# Sheet1.net
KiCad netlist of a schematic drawn in Altium Designer
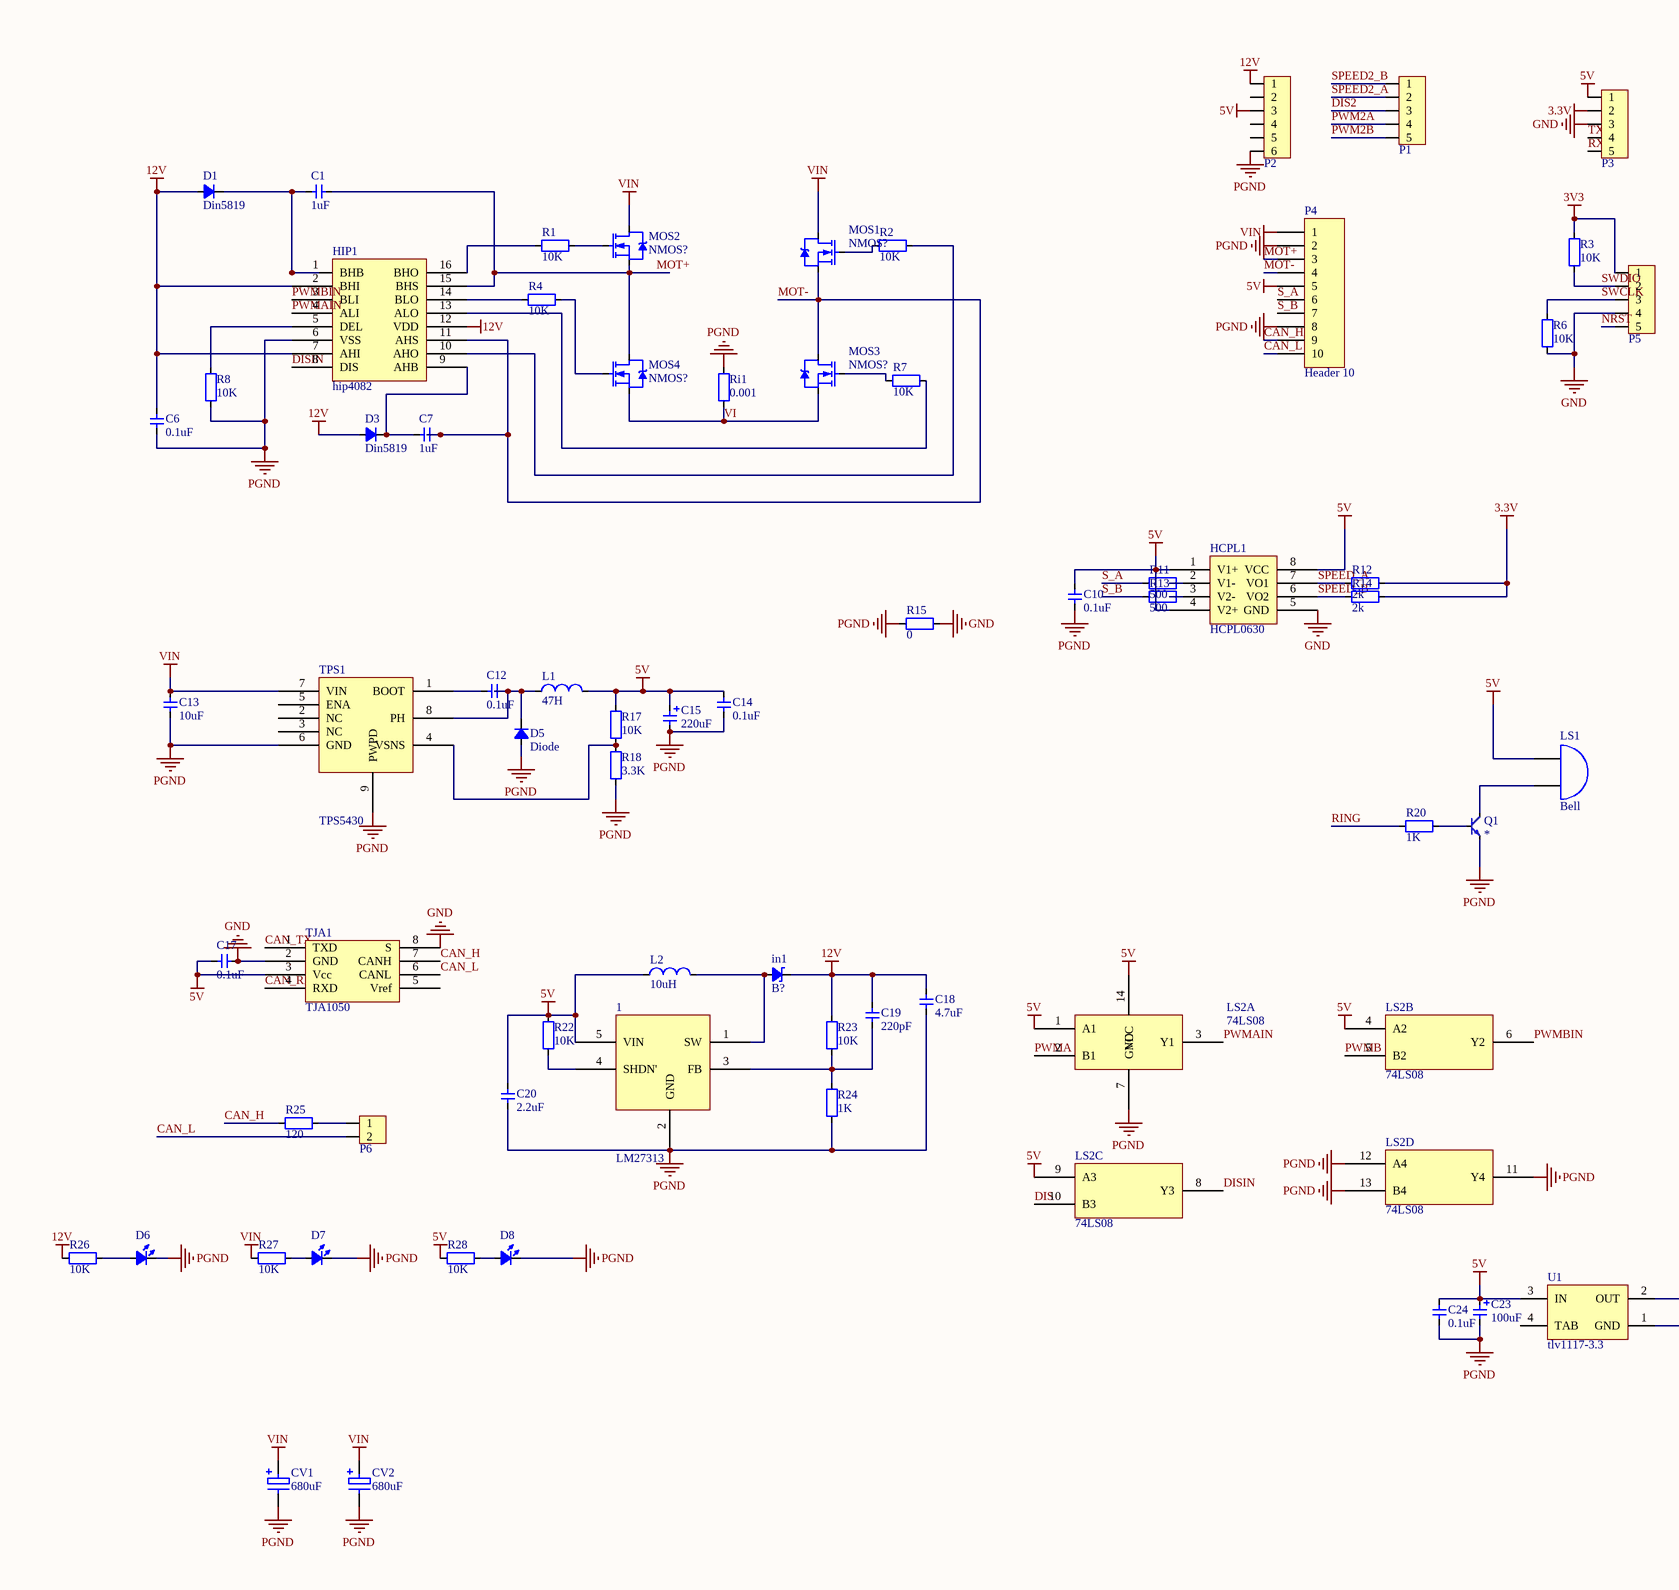
[diagram p0: Sheet1.SchDoc, left]
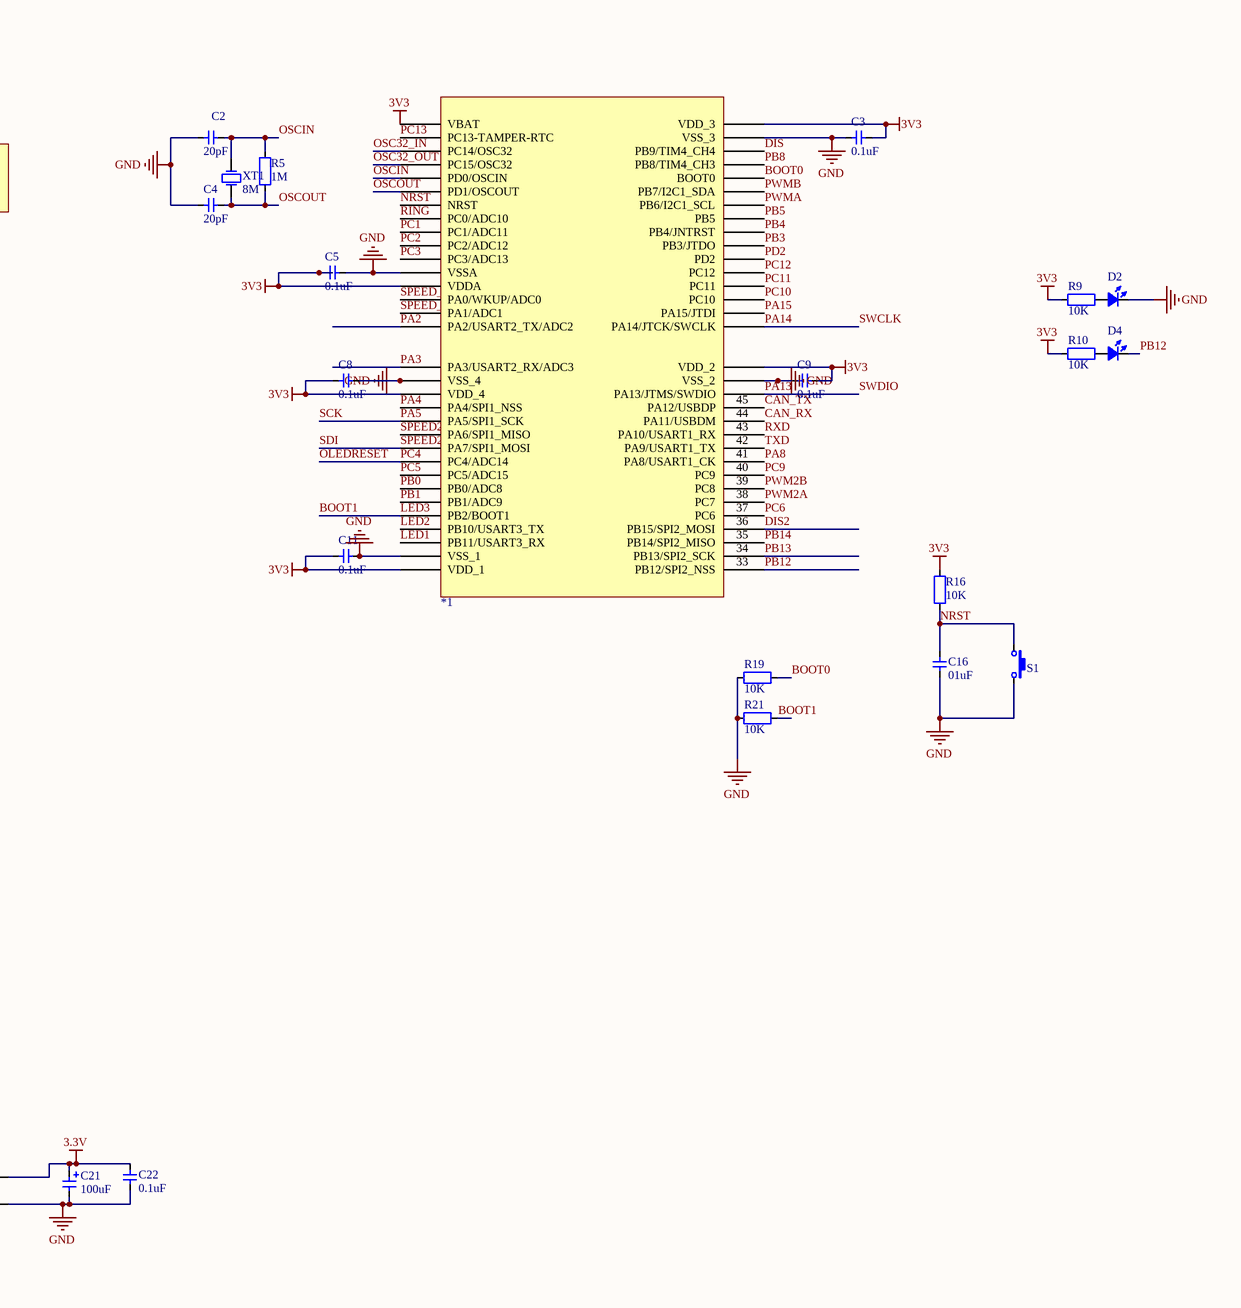
[diagram p1: Sheet1.SchDoc, right]

(export (version "E")
  (design (tool "Eeschema 10.0.6"))
  (components
    (comp (ref "*1")
      (value "STM32F103RC")
      (footprint "LQFP_P0.5_64")
      (description "MCU")
      (libsource (lib "Integrated_Library") (part "STM32F103RC"))
    )
    (comp (ref "1")
      (value "LM27313")
      (footprint "SOT23-5")
      (libsource (lib "K60-mainboard-v3.1") (part "LM27313"))
    )
    (comp (ref "C1")
      (value "1uF")
      (footprint "CAP_0603")
      (description "Capacitor")
      (fields (field (name "Comment") "Cap_0603"))
      (libsource (lib "Integrated_Library") (part "Cap_0603"))
    )
    (comp (ref "C2")
      (value "20pF")
      (footprint "CAP_0603")
      (description "Capacitor")
      (fields (field (name "Comment") "Cap_0603"))
      (libsource (lib "Integrated_Library") (part "Cap_0603"))
    )
    (comp (ref "C3")
      (value "0.1uF")
      (footprint "CAP_0603")
      (description "Capacitor")
      (fields (field (name "Comment") "Cap_0603"))
      (libsource (lib "Integrated_Library") (part "Cap_0603"))
    )
    (comp (ref "C4")
      (value "20pF")
      (footprint "CAP_0603")
      (description "Capacitor")
      (fields (field (name "Comment") "Cap_0603"))
      (libsource (lib "Integrated_Library") (part "Cap_0603"))
    )
    (comp (ref "C5")
      (value "0.1uF")
      (footprint "CAP_0603")
      (description "Capacitor")
      (fields (field (name "Comment") "Cap_0603"))
      (libsource (lib "Integrated_Library") (part "Cap_0603"))
    )
    (comp (ref "C6")
      (value "0.1uF")
      (footprint "CAP_0603")
      (description "Capacitor")
      (fields (field (name "Comment") "Cap_0603"))
      (libsource (lib "Integrated_Library") (part "Cap_0603"))
    )
    (comp (ref "C7")
      (value "1uF")
      (footprint "CAP_0603")
      (description "Capacitor")
      (fields (field (name "Comment") "Cap_0603"))
      (libsource (lib "Integrated_Library") (part "Cap_0603"))
    )
    (comp (ref "C8")
      (value "0.1uF")
      (footprint "CAP_0603")
      (description "Capacitor")
      (fields (field (name "Comment") "Cap_0603"))
      (libsource (lib "Integrated_Library") (part "Cap_0603"))
    )
    (comp (ref "C9")
      (value "0.1uF")
      (footprint "CAP_0603")
      (description "Capacitor")
      (fields (field (name "Comment") "Cap_0603"))
      (libsource (lib "Integrated_Library") (part "Cap_0603"))
    )
    (comp (ref "C10")
      (value "0.1uF")
      (footprint "CAP_0603")
      (description "Capacitor")
      (fields (field (name "Comment") "Cap_0603"))
      (libsource (lib "Integrated_Library") (part "Cap_0603"))
    )
    (comp (ref "C11")
      (value "0.1uF")
      (footprint "CAP_0603")
      (description "Capacitor")
      (fields (field (name "Comment") "Cap_0603"))
      (libsource (lib "Integrated_Library") (part "Cap_0603"))
    )
    (comp (ref "C12")
      (value "0.1uF")
      (footprint "CAP_0603")
      (description "Capacitor")
      (fields (field (name "Comment") "Cap_0603"))
      (libsource (lib "Integrated_Library") (part "Cap_0603"))
    )
    (comp (ref "C13")
      (value "10uF")
      (footprint "CAP_0603")
      (description "Capacitor")
      (fields (field (name "Comment") "Cap_0603"))
      (libsource (lib "Integrated_Library") (part "Cap_0603"))
    )
    (comp (ref "C14")
      (value "0.1uF")
      (footprint "CAP_0603")
      (description "Capacitor")
      (fields (field (name "Comment") "Cap_0603"))
      (libsource (lib "Integrated_Library") (part "Cap_0603"))
    )
    (comp (ref "C15")
      (value "220uF")
      (footprint "CAP_TAN_P0805")
      (description "Capacitor")
      (fields (field (name "Comment") "Cap_Tan_0805"))
      (libsource (lib "Integrated_Library") (part "Cap_Tan_0805"))
    )
    (comp (ref "C16")
      (value "01uF")
      (footprint "CAP_0603")
      (description "Capacitor")
      (fields (field (name "Comment") "Cap_0603"))
      (libsource (lib "Integrated_Library") (part "Cap_0603"))
    )
    (comp (ref "C17")
      (value "0.1uF")
      (footprint "CAP_0603")
      (description "Capacitor")
      (fields (field (name "Comment") "Cap_0603"))
      (libsource (lib "Integrated_Library") (part "Cap_0603"))
    )
    (comp (ref "C18")
      (value "4.7uF")
      (footprint "CAP_0603")
      (description "Capacitor")
      (fields (field (name "Comment") "Cap_0603"))
      (libsource (lib "Integrated_Library") (part "Cap_0603"))
    )
    (comp (ref "C19")
      (value "220pF")
      (footprint "CAP_0603")
      (description "Capacitor")
      (fields (field (name "Comment") "Cap_0603"))
      (libsource (lib "Integrated_Library") (part "Cap_0603"))
    )
    (comp (ref "C20")
      (value "2.2uF")
      (footprint "CAP_0603")
      (description "Capacitor")
      (fields (field (name "Comment") "Cap_0603"))
      (libsource (lib "Integrated_Library") (part "Cap_0603"))
    )
    (comp (ref "C21")
      (value "100uF")
      (footprint "CAP_TAN_P0805")
      (description "Capacitor")
      (fields (field (name "Comment") "Cap_Tan_0805"))
      (libsource (lib "Integrated_Library") (part "Cap_Tan_0805"))
    )
    (comp (ref "C22")
      (value "0.1uF")
      (footprint "CAP_0603")
      (description "Capacitor")
      (fields (field (name "Comment") "Cap_0603"))
      (libsource (lib "Integrated_Library") (part "Cap_0603"))
    )
    (comp (ref "C23")
      (value "100uF")
      (footprint "CAP_TAN_P0805")
      (description "Capacitor")
      (fields (field (name "Comment") "Cap_Tan_0805"))
      (libsource (lib "Integrated_Library") (part "Cap_Tan_0805"))
    )
    (comp (ref "C24")
      (value "0.1uF")
      (footprint "CAP_0603")
      (description "Capacitor")
      (fields (field (name "Comment") "Cap_0603"))
      (libsource (lib "Integrated_Library") (part "Cap_0603"))
    )
    (comp (ref "CV1")
      (value "680uF")
      (footprint "电解电容器")
      (description "电解电容")
      (fields (field (name "PUBLISHER") "Altium Limited"))
      (libsource (lib "Libraries_2014_0618") (part "CAP-ELE"))
    )
    (comp (ref "CV2")
      (value "680uF")
      (footprint "电解电容器")
      (description "电解电容")
      (fields (field (name "PUBLISHER") "Altium Limited"))
      (libsource (lib "Libraries_2014_0618") (part "CAP-ELE"))
    )
    (comp (ref "D1")
      (value "Din5819")
      (footprint "LED_0805_RED")
      (description "Diode")
      (libsource (lib "Integrated_Library") (part "Diode"))
    )
    (comp (ref "D2")
      (value "LED_0805")
      (footprint "LED_0805_RED")
      (description "LED")
      (libsource (lib "Integrated_Library") (part "LED_0805"))
    )
    (comp (ref "D3")
      (value "Din5819")
      (footprint "LED_0805_RED")
      (description "Diode")
      (libsource (lib "Integrated_Library") (part "Diode"))
    )
    (comp (ref "D4")
      (value "LED_0805")
      (footprint "LED_0805_RED")
      (description "LED")
      (libsource (lib "Integrated_Library") (part "LED_0805"))
    )
    (comp (ref "D5") (value "Diode") (footprint "LED_0805_RED") (libsource (lib "SCH_Active") (part "Diode")))
    (comp (ref "D6")
      (value "LED_0603")
      (footprint "PCB_ActiveLED:LED_0603_RED")
      (description "LED")
      (libsource (lib "SCH_Active") (part "LED_0603"))
    )
    (comp (ref "D7")
      (value "LED_0603")
      (footprint "PCB_ActiveLED:LED_0603_RED")
      (description "LED")
      (libsource (lib "SCH_Active") (part "LED_0603"))
    )
    (comp (ref "D8")
      (value "LED_0603")
      (footprint "PCB_ActiveLED:LED_0603_RED")
      (description "LED")
      (libsource (lib "SCH_Active") (part "LED_0603"))
    )
    (comp (ref "HCPL1")
      (value "HCPL0630")
      (footprint "SOP_E150_8")
      (libsource (lib "K60-mainboard-v3.1") (part "HCPL0630"))
    )
    (comp (ref "HIP1") (value "hip4082") (footprint "SOP_E150_16") (libsource (lib "元件库") (part "hip4082")))
    (comp (ref "in1")
      (value "B?")
      (footprint "PCB_ActiveDIO:SOD-123")
      (description "Diode")
      (fields (field (name "Comment") "SchottkyDiode_SOD123"))
      (libsource (lib "SCH_Active") (part "SchottkyDiode_SOD123"))
    )
    (comp (ref "L1")
      (value "47H")
      (footprint "IND_0603")
      (description "Inductor")
      (fields (field (name "Comment") "Ind_0603"))
      (libsource (lib "Integrated_Library") (part "Ind_0603"))
    )
    (comp (ref "L2")
      (value "10uH")
      (footprint "IND_0603")
      (description "Inductor")
      (fields (field (name "Comment") "Ind_0603"))
      (libsource (lib "Integrated_Library") (part "Ind_0603"))
    )
    (comp (ref "LS1")
      (value "Bell")
      (footprint "Bell-5.6-0.6-9mm")
      (description "Electrical Bell")
      (fields (field (name "PUBLISHER") "Altium Limited"))
      (libsource (lib "附加元件") (part "Bell"))
    )
    (comp (ref "LS2")
      (value "74LS08")
      (footprint "SOP14")
      (libsource (lib "K60-mainboard-v3.1") (part "74LS08"))
    )
    (comp (ref "MOS1")
      (value "NMOS?")
      (footprint "PCB_IntegratedCircuit:TO-252AA")
      (description "MOSFET")
      (fields (field (name "Comment") "MOSFET_N"))
      (libsource (lib "SCH_Active") (part "MOSFET_N"))
    )
    (comp (ref "MOS2")
      (value "NMOS?")
      (footprint "PCB_IntegratedCircuit:TO-252AA")
      (description "MOSFET")
      (fields (field (name "Comment") "MOSFET_N"))
      (libsource (lib "SCH_Active") (part "MOSFET_N"))
    )
    (comp (ref "MOS3")
      (value "NMOS?")
      (footprint "PCB_IntegratedCircuit:TO-252AA")
      (description "MOSFET")
      (fields (field (name "Comment") "MOSFET_N"))
      (libsource (lib "SCH_Active") (part "MOSFET_N"))
    )
    (comp (ref "MOS4")
      (value "NMOS?")
      (footprint "PCB_IntegratedCircuit:TO-252AA")
      (description "MOSFET")
      (fields (field (name "Comment") "MOSFET_N"))
      (libsource (lib "SCH_Active") (part "MOSFET_N"))
    )
    (comp (ref "P1")
      (value "HDR1x5_2.54")
      (footprint "HDR1X5_2.54_180")
      (description "Header")
      (libsource (lib "Integrated_Library") (part "HDR1x5_2.54"))
    )
    (comp (ref "P2")
      (value "HDR1x6_2.54")
      (footprint "HDR1X6_2.54_180")
      (description "Header")
      (libsource (lib "Integrated_Library") (part "HDR1x6_2.54"))
    )
    (comp (ref "P3")
      (value "HDR1x5_2.54")
      (footprint "Green_5P")
      (description "Header")
      (libsource (lib "Integrated_Library") (part "HDR1x5_2.54"))
    )
    (comp (ref "P4")
      (value "Header 10")
      (footprint "Green_10P")
      (description "Header, 10-Pin")
      (fields (field (name "PUBLISHER") "Altium Limited"))
      (libsource (lib "Libraries_2014_0618") (part "Header 10"))
    )
    (comp (ref "P5")
      (value "HDR1x5_2.54")
      (footprint "HDR1X5_2.54_180")
      (description "Header")
      (libsource (lib "Integrated_Library") (part "HDR1x5_2.54"))
    )
    (comp (ref "P6")
      (value "HDR1x2_2.54")
      (footprint "HDR1X2_2.54_180")
      (description "Header")
      (libsource (lib "Integrated_Library") (part "HDR1x2_2.54"))
    )
    (comp (ref "Q1")
      (value "BJT_NPN")
      (footprint "SOT23-3")
      (description "Transistor")
      (fields (field (name "ALTIUM_VALUE") "*"))
      (libsource (lib "Integrated_Library") (part "BJT_NPN"))
    )
    (comp (ref "R1")
      (value "10K")
      (footprint "RES_0603")
      (description "Resistor")
      (fields (field (name "Comment") "Res_0603"))
      (libsource (lib "Integrated_Library") (part "Res_0603"))
    )
    (comp (ref "R2")
      (value "10K")
      (footprint "RES_0603")
      (description "Resistor")
      (fields (field (name "Comment") "Res_0603"))
      (libsource (lib "Integrated_Library") (part "Res_0603"))
    )
    (comp (ref "R3")
      (value "10K")
      (footprint "RES_0603")
      (description "Resistor")
      (fields (field (name "Comment") "Res_0603"))
      (libsource (lib "") (part "Res_0603_2"))
    )
    (comp (ref "R4")
      (value "10K")
      (footprint "RES_0603")
      (description "Resistor")
      (fields (field (name "Comment") "Res_0603"))
      (libsource (lib "Integrated_Library") (part "Res_0603"))
    )
    (comp (ref "R5")
      (value "1M")
      (footprint "RES_0603")
      (description "Resistor")
      (fields (field (name "Comment") "Res_0603"))
      (libsource (lib "") (part "Res_0603_2"))
    )
    (comp (ref "R6")
      (value "10K")
      (footprint "RES_0603")
      (description "Resistor")
      (fields (field (name "Comment") "Res_0603"))
      (libsource (lib "") (part "Res_0603_2"))
    )
    (comp (ref "R7")
      (value "10K")
      (footprint "RES_0603")
      (description "Resistor")
      (fields (field (name "Comment") "Res_0603"))
      (libsource (lib "Integrated_Library") (part "Res_0603"))
    )
    (comp (ref "R8")
      (value "10K")
      (footprint "RES_0603")
      (description "Resistor")
      (fields (field (name "Comment") "Res_0603"))
      (libsource (lib "") (part "Res_0603_2"))
    )
    (comp (ref "R9")
      (value "10K")
      (footprint "RES_0603")
      (description "Resistor")
      (fields (field (name "Comment") "Res_0603"))
      (libsource (lib "Integrated_Library") (part "Res_0603"))
    )
    (comp (ref "R10")
      (value "10K")
      (footprint "RES_0603")
      (description "Resistor")
      (fields (field (name "Comment") "Res_0603"))
      (libsource (lib "Integrated_Library") (part "Res_0603"))
    )
    (comp (ref "R11")
      (value "500")
      (footprint "RES_0603")
      (description "Resistor")
      (fields (field (name "Comment") "Res_0603"))
      (libsource (lib "") (part "Res_0603_1"))
    )
    (comp (ref "R12")
      (value "2k")
      (footprint "RES_0603")
      (description "Resistor")
      (fields (field (name "Comment") "Res_0603"))
      (libsource (lib "") (part "Res_0603_1"))
    )
    (comp (ref "R13")
      (value "500")
      (footprint "RES_0603")
      (description "Resistor")
      (fields (field (name "Comment") "Res_0603"))
      (libsource (lib "") (part "Res_0603_1"))
    )
    (comp (ref "R14")
      (value "2k")
      (footprint "RES_0603")
      (description "Resistor")
      (fields (field (name "Comment") "Res_0603"))
      (libsource (lib "") (part "Res_0603_1"))
    )
    (comp (ref "R15")
      (value "0")
      (footprint "RES_0603")
      (description "Resistor")
      (fields (field (name "Comment") "Res_0603"))
      (libsource (lib "Integrated_Library") (part "Res_0603"))
    )
    (comp (ref "R16")
      (value "10K")
      (footprint "RES_0603")
      (description "Resistor")
      (fields (field (name "Comment") "Res_0603"))
      (libsource (lib "") (part "Res_0603_2"))
    )
    (comp (ref "R17")
      (value "10K")
      (footprint "RES_0603")
      (description "Resistor")
      (fields (field (name "Comment") "Res_0603"))
      (libsource (lib "") (part "Res_0603_2"))
    )
    (comp (ref "R18")
      (value "3.3K")
      (footprint "RES_0603")
      (description "Resistor")
      (fields (field (name "Comment") "Res_0603"))
      (libsource (lib "") (part "Res_0603_2"))
    )
    (comp (ref "R19")
      (value "10K")
      (footprint "RES_0603")
      (description "Resistor")
      (fields (field (name "Comment") "Res_0603"))
      (libsource (lib "") (part "Res_0603_1"))
    )
    (comp (ref "R20")
      (value "1K")
      (footprint "RES_0603")
      (description "Resistor")
      (fields (field (name "Comment") "Res_0603"))
      (libsource (lib "Integrated_Library") (part "Res_0603"))
    )
    (comp (ref "R21")
      (value "10K")
      (footprint "RES_0603")
      (description "Resistor")
      (fields (field (name "Comment") "Res_0603"))
      (libsource (lib "") (part "Res_0603_1"))
    )
    (comp (ref "R22")
      (value "10K")
      (footprint "RES_0603")
      (description "Resistor")
      (fields (field (name "Comment") "Res_0603"))
      (libsource (lib "") (part "Res_0603_2"))
    )
    (comp (ref "R23")
      (value "10K")
      (footprint "RES_0603")
      (description "Resistor")
      (fields (field (name "Comment") "Res_0603"))
      (libsource (lib "") (part "Res_0603_2"))
    )
    (comp (ref "R24")
      (value "1K")
      (footprint "RES_0603")
      (description "Resistor")
      (fields (field (name "Comment") "Res_0603"))
      (libsource (lib "") (part "Res_0603_2"))
    )
    (comp (ref "R25")
      (value "120")
      (footprint "RES_0603")
      (description "Resistor")
      (fields (field (name "Comment") "Res_0603"))
      (libsource (lib "Integrated_Library") (part "Res_0603"))
    )
    (comp (ref "R26")
      (value "10K")
      (footprint "RES_0603")
      (description "Resistor")
      (fields (field (name "Comment") "Res_0603"))
      (libsource (lib "Integrated_Library") (part "Res_0603"))
    )
    (comp (ref "R27")
      (value "10K")
      (footprint "RES_0603")
      (description "Resistor")
      (fields (field (name "Comment") "Res_0603"))
      (libsource (lib "Integrated_Library") (part "Res_0603"))
    )
    (comp (ref "R28")
      (value "10K")
      (footprint "RES_0603")
      (description "Resistor")
      (fields (field (name "Comment") "Res_0603"))
      (libsource (lib "Integrated_Library") (part "Res_0603"))
    )
    (comp (ref "Ri1")
      (value "0.001")
      (footprint "RES_0603")
      (description "Resistor")
      (fields (field (name "Comment") "Res_0603"))
      (libsource (lib "") (part "Res_0603_2"))
    )
    (comp (ref "S1")
      (value "ButtonTACT_3x6x2.5_180")
      (footprint "ButtonTACT_3x6x2.5_180")
      (description "Button")
      (libsource (lib "Integrated_Library") (part "ButtonTACT_3x6x2.5_180"))
    )
    (comp (ref "TJA1")
      (value "TJA1050")
      (footprint "SOP_E150_8")
      (description "CAN总线收发器")
      (libsource (lib "Libraries_2014_0618") (part "TJA1050"))
    )
    (comp (ref "TPS1")
      (value "TPS5430")
      (footprint "SOP_E150_9")
      (libsource (lib "K60-mainboard-v3.1") (part "TPS5430"))
    )
    (comp (ref "U1")
      (value "tlv1117-3.3")
      (footprint "SOT223-3")
      (description "800mA Low-Dropout Linear Regulator")
      (fields
        (field (name "PARTNUMBER") "LM1117IMP-5.0")
        (field (name "MANUFACTURER") "National Semiconductor")
        (field (name "PUBLISHER") "Altium Limited")
      )
      (libsource (lib "K60-mainboard-v3.1") (part "LM1117IMP-5.0"))
    )
    (comp (ref "XT1")
      (value "8M")
      (footprint "XT_5032_2")
      (description "Crystal Oscillator")
      (fields (field (name "Comment") "XTAL_32.768kHz"))
      (libsource (lib "Integrated_Library") (part "XTAL_32.768k"))
    )
  )
  (nets
    (net (code "1") (name "/BOOT0") (class "Default")
      (node (ref "*1") (pin "60") (pinfunction "BOOT0_60") (pintype "passive"))
      (node (ref "R19") (pin "1") (pinfunction "1_1") (pintype "passive"))
    )
    (net (code "2") (name "/BOOT1") (class "Default")
      (node (ref "*1") (pin "28") (pinfunction "PB2/BOOT1_28") (pintype "passive"))
      (node (ref "R21") (pin "1") (pinfunction "1_1") (pintype "passive"))
    )
    (net (code "3") (name "/CAN_H") (class "Default")
      (node (ref "P4") (pin "9") (pinfunction "9_9") (pintype "passive"))
      (node (ref "R25") (pin "1") (pinfunction "1_1") (pintype "passive"))
      (node (ref "TJA1") (pin "7") (pinfunction "CANH_7") (pintype "passive"))
    )
    (net (code "4") (name "/CAN_L") (class "Default")
      (node (ref "P4") (pin "10") (pinfunction "10_10") (pintype "passive"))
      (node (ref "P6") (pin "2") (pinfunction "2_2") (pintype "passive"))
      (node (ref "TJA1") (pin "6") (pinfunction "CANL_6") (pintype "passive"))
    )
    (net (code "5") (name "/CAN_RX") (class "Default")
      (node (ref "*1") (pin "44") (pinfunction "PA11/USBDM_44") (pintype "passive"))
      (node (ref "TJA1") (pin "4") (pinfunction "RXD_4") (pintype "passive"))
    )
    (net (code "6") (name "/CAN_TX") (class "Default")
      (node (ref "*1") (pin "45") (pinfunction "PA12/USBDP_45") (pintype "passive"))
      (node (ref "TJA1") (pin "1") (pinfunction "TXD_1") (pintype "passive"))
    )
    (net (code "7") (name "/DIS") (class "Default")
      (node (ref "*1") (pin "62") (pinfunction "PB9/TIM4_CH4_62") (pintype "passive"))
      (node (ref "LS2") (pin "10") (pinfunction "B3_10") (pintype "passive"))
    )
    (net (code "8") (name "/DIS2") (class "Default")
      (node (ref "*1") (pin "36") (pinfunction "PB15/SPI2_MOSI_36") (pintype "passive"))
      (node (ref "P1") (pin "3") (pinfunction "3_3") (pintype "passive"))
    )
    (net (code "9") (name "/DISIN") (class "Default")
      (node (ref "HIP1") (pin "8") (pinfunction "DIS_8") (pintype "passive"))
      (node (ref "LS2") (pin "8") (pinfunction "Y3_8") (pintype "passive"))
    )
    (net (code "10") (name "/LED1") (class "Default")
      (node (ref "*1") (pin "30") (pinfunction "PB11/USART3_RX_30") (pintype "passive"))
    )
    (net (code "11") (name "/LED2") (class "Default")
      (node (ref "*1") (pin "29") (pinfunction "PB10/USART3_TX_29") (pintype "passive"))
    )
    (net (code "12") (name "/MOT+") (class "Default")
      (node (ref "C1") (pin "2") (pinfunction "2_2") (pintype "passive"))
      (node (ref "HIP1") (pin "15") (pinfunction "BHS_15") (pintype "passive"))
      (node (ref "MOS2") (pin "3") (pinfunction "S_3") (pintype "passive"))
      (node (ref "MOS4") (pin "4") (pinfunction "D_4") (pintype "passive"))
      (node (ref "P4") (pin "3") (pinfunction "3_3") (pintype "passive"))
    )
    (net (code "13") (name "/MOT-") (class "Default")
      (node (ref "C7") (pin "2") (pinfunction "2_2") (pintype "passive"))
      (node (ref "HIP1") (pin "11") (pinfunction "AHS_11") (pintype "passive"))
      (node (ref "MOS1") (pin "3") (pinfunction "S_3") (pintype "passive"))
      (node (ref "MOS3") (pin "4") (pinfunction "D_4") (pintype "passive"))
      (node (ref "P4") (pin "4") (pinfunction "4_4") (pintype "passive"))
    )
    (net (code "14") (name "/NRST") (class "Default")
      (node (ref "*1") (pin "7") (pinfunction "NRST_7") (pintype "passive"))
      (node (ref "C16") (pin "2") (pinfunction "2_2") (pintype "passive"))
      (node (ref "P5") (pin "5") (pinfunction "5_5") (pintype "passive"))
      (node (ref "R16") (pin "1") (pinfunction "1_1") (pintype "passive"))
      (node (ref "S1") (pin "1") (pinfunction "1_1") (pintype "passive"))
    )
    (net (code "15") (name "/OLEDRESET") (class "Default")
      (node (ref "*1") (pin "24") (pinfunction "PC4/ADC14_24") (pintype "passive"))
    )
    (net (code "16") (name "/OSC32_IN") (class "Default")
      (node (ref "*1") (pin "3") (pinfunction "PC14/OSC32_3") (pintype "passive"))
    )
    (net (code "17") (name "/OSC32_OUT") (class "Default")
      (node (ref "*1") (pin "4") (pinfunction "PC15/OSC32_4") (pintype "passive"))
    )
    (net (code "18") (name "/OSCIN") (class "Default")
      (node (ref "*1") (pin "5") (pinfunction "PD0/OSCIN_5") (pintype "passive"))
      (node (ref "C2") (pin "2") (pinfunction "2_2") (pintype "passive"))
      (node (ref "R5") (pin "2") (pinfunction "2_2") (pintype "passive"))
      (node (ref "XT1") (pin "2") (pinfunction "OSC2_2") (pintype "passive"))
    )
    (net (code "19") (name "/OSCOUT") (class "Default")
      (node (ref "*1") (pin "6") (pinfunction "PD1/OSCOUT_6") (pintype "passive"))
      (node (ref "C4") (pin "2") (pinfunction "2_2") (pintype "passive"))
      (node (ref "R5") (pin "1") (pinfunction "1_1") (pintype "passive"))
      (node (ref "XT1") (pin "1") (pinfunction "OSC1_1") (pintype "passive"))
    )
    (net (code "20") (name "/PA2") (class "Default")
      (node (ref "*1") (pin "16") (pinfunction "PA2/USART2_TX/ADC2_16") (pintype "passive"))
    )
    (net (code "21") (name "/PA3") (class "Default")
      (node (ref "*1") (pin "17") (pinfunction "PA3/USART2_RX/ADC3_17") (pintype "passive"))
    )
    (net (code "22") (name "/PA4") (class "Default")
      (node (ref "*1") (pin "20") (pinfunction "PA4/SPI1_NSS_20") (pintype "passive"))
    )
    (net (code "23") (name "/PA5") (class "Default")
      (node (ref "*1") (pin "21") (pinfunction "PA5/SPI1_SCK_21") (pintype "passive"))
    )
    (net (code "24") (name "/PA8") (class "Default")
      (node (ref "*1") (pin "41") (pinfunction "PA8/USART1_CK_41") (pintype "passive"))
    )
    (net (code "25") (name "/PA13") (class "Default")
      (node (ref "*1") (pin "46") (pinfunction "PA13/JTMS/SWDIO_46") (pintype "passive"))
      (node (ref "P5") (pin "2") (pinfunction "2_2") (pintype "passive"))
      (node (ref "R3") (pin "1") (pinfunction "1_1") (pintype "passive"))
    )
    (net (code "26") (name "/PA14") (class "Default")
      (node (ref "*1") (pin "49") (pinfunction "PA14/JTCK/SWCLK_49") (pintype "passive"))
      (node (ref "P5") (pin "3") (pinfunction "3_3") (pintype "passive"))
      (node (ref "R6") (pin "2") (pinfunction "2_2") (pintype "passive"))
    )
    (net (code "27") (name "/PA15") (class "Default")
      (node (ref "*1") (pin "50") (pinfunction "PA15/JTDI_50") (pintype "passive"))
    )
    (net (code "28") (name "/PB0") (class "Default")
      (node (ref "*1") (pin "26") (pinfunction "PB0/ADC8_26") (pintype "passive"))
    )
    (net (code "29") (name "/PB1") (class "Default")
      (node (ref "*1") (pin "27") (pinfunction "PB1/ADC9_27") (pintype "passive"))
    )
    (net (code "30") (name "/PB3") (class "Default")
      (node (ref "*1") (pin "55") (pinfunction "PB3/JTDO_55") (pintype "passive"))
    )
    (net (code "31") (name "/PB4") (class "Default")
      (node (ref "*1") (pin "56") (pinfunction "PB4/JNTRST_56") (pintype "passive"))
    )
    (net (code "32") (name "/PB5") (class "Default")
      (node (ref "*1") (pin "57") (pinfunction "PB5_57") (pintype "passive"))
    )
    (net (code "33") (name "/PB8") (class "Default")
      (node (ref "*1") (pin "61") (pinfunction "PB8/TIM4_CH3_61") (pintype "passive"))
    )
    (net (code "34") (name "/PB12") (class "Default")
      (node (ref "*1") (pin "33") (pinfunction "PB12/SPI2_NSS_33") (pintype "passive"))
      (node (ref "D4") (pin "2") (pinfunction "K_2") (pintype "passive"))
    )
    (net (code "35") (name "/PB13") (class "Default")
      (node (ref "*1") (pin "34") (pinfunction "PB13/SPI2_SCK_34") (pintype "passive"))
    )
    (net (code "36") (name "/PB14") (class "Default")
      (node (ref "*1") (pin "35") (pinfunction "PB14/SPI2_MISO_35") (pintype "passive"))
    )
    (net (code "37") (name "/PC1") (class "Default")
      (node (ref "*1") (pin "9") (pinfunction "PC1/ADC11_9") (pintype "passive"))
    )
    (net (code "38") (name "/PC2") (class "Default")
      (node (ref "*1") (pin "10") (pinfunction "PC2/ADC12_10") (pintype "passive"))
    )
    (net (code "39") (name "/PC3") (class "Default")
      (node (ref "*1") (pin "11") (pinfunction "PC3/ADC13_11") (pintype "passive"))
    )
    (net (code "40") (name "/PC5") (class "Default")
      (node (ref "*1") (pin "25") (pinfunction "PC5/ADC15_25") (pintype "passive"))
    )
    (net (code "41") (name "/PC6") (class "Default")
      (node (ref "*1") (pin "37") (pinfunction "PC6_37") (pintype "passive"))
    )
    (net (code "42") (name "/PC9") (class "Default")
      (node (ref "*1") (pin "40") (pinfunction "PC9_40") (pintype "passive"))
    )
    (net (code "43") (name "/PC10") (class "Default")
      (node (ref "*1") (pin "51") (pinfunction "PC10_51") (pintype "passive"))
    )
    (net (code "44") (name "/PC11") (class "Default")
      (node (ref "*1") (pin "52") (pinfunction "PC11_52") (pintype "passive"))
    )
    (net (code "45") (name "/PC12") (class "Default")
      (node (ref "*1") (pin "53") (pinfunction "PC12_53") (pintype "passive"))
    )
    (net (code "46") (name "/PC13") (class "Default")
      (node (ref "*1") (pin "2") (pinfunction "PC13-TAMPER-RTC_2") (pintype "passive"))
    )
    (net (code "47") (name "/PD2") (class "Default")
      (node (ref "*1") (pin "54") (pinfunction "PD2_54") (pintype "passive"))
    )
    (net (code "48") (name "/PWM2A") (class "Default")
      (node (ref "*1") (pin "38") (pinfunction "PC7_38") (pintype "passive"))
      (node (ref "P1") (pin "4") (pinfunction "4_4") (pintype "passive"))
    )
    (net (code "49") (name "/PWM2B") (class "Default")
      (node (ref "*1") (pin "39") (pinfunction "PC8_39") (pintype "passive"))
      (node (ref "P1") (pin "5") (pinfunction "5_5") (pintype "passive"))
    )
    (net (code "50") (name "/PWMA") (class "Default")
      (node (ref "*1") (pin "58") (pinfunction "PB6/I2C1_SCL_58") (pintype "passive"))
      (node (ref "LS2") (pin "2") (pinfunction "B1_2") (pintype "passive"))
    )
    (net (code "51") (name "/PWMAIN") (class "Default")
      (node (ref "HIP1") (pin "4") (pinfunction "ALI_4") (pintype "passive"))
      (node (ref "LS2") (pin "3") (pinfunction "Y1_3") (pintype "passive"))
    )
    (net (code "52") (name "/PWMB") (class "Default")
      (node (ref "*1") (pin "59") (pinfunction "PB7/I2C1_SDA_59") (pintype "passive"))
      (node (ref "LS2") (pin "5") (pinfunction "B2_5") (pintype "passive"))
    )
    (net (code "53") (name "/PWMBIN") (class "Default")
      (node (ref "HIP1") (pin "3") (pinfunction "BLI_3") (pintype "passive"))
      (node (ref "LS2") (pin "6") (pinfunction "Y2_6") (pintype "passive"))
    )
    (net (code "54") (name "/RING") (class "Default")
      (node (ref "*1") (pin "8") (pinfunction "PC0/ADC10_8") (pintype "passive"))
      (node (ref "R20") (pin "1") (pinfunction "1_1") (pintype "passive"))
    )
    (net (code "55") (name "/RXD") (class "Default")
      (node (ref "*1") (pin "43") (pinfunction "PA10/USART1_RX_43") (pintype "passive"))
      (node (ref "P3") (pin "5") (pinfunction "5_5") (pintype "passive"))
    )
    (net (code "56") (name "/SDI") (class "Default")
      (node (ref "*1") (pin "23") (pinfunction "PA7/SPI1_MOSI_23") (pintype "passive"))
      (node (ref "P1") (pin "1") (pinfunction "1_1") (pintype "passive"))
    )
    (net (code "57") (name "/SPEED2_A") (class "Default")
      (node (ref "*1") (pin "22") (pinfunction "PA6/SPI1_MISO_22") (pintype "passive"))
      (node (ref "P1") (pin "2") (pinfunction "2_2") (pintype "passive"))
    )
    (net (code "58") (name "/SPEED_A") (class "Default")
      (node (ref "*1") (pin "14") (pinfunction "PA0/WKUP/ADC0_14") (pintype "passive"))
      (node (ref "HCPL1") (pin "7") (pinfunction "VO1_7") (pintype "passive"))
      (node (ref "R12") (pin "2") (pinfunction "2_2") (pintype "passive"))
    )
    (net (code "59") (name "/SPEED_B") (class "Default")
      (node (ref "*1") (pin "15") (pinfunction "PA1/ADC1_15") (pintype "passive"))
      (node (ref "HCPL1") (pin "6") (pinfunction "VO2_6") (pintype "passive"))
      (node (ref "R14") (pin "2") (pinfunction "2_2") (pintype "passive"))
    )
    (net (code "60") (name "/S_A") (class "Default")
      (node (ref "P4") (pin "6") (pinfunction "6_6") (pintype "passive"))
      (node (ref "R11") (pin "2") (pinfunction "2_2") (pintype "passive"))
    )
    (net (code "61") (name "/S_B") (class "Default")
      (node (ref "P4") (pin "7") (pinfunction "7_7") (pintype "passive"))
      (node (ref "R13") (pin "2") (pinfunction "2_2") (pintype "passive"))
    )
    (net (code "62") (name "/TXD") (class "Default")
      (node (ref "*1") (pin "42") (pinfunction "PA9/USART1_TX_42") (pintype "passive"))
      (node (ref "P3") (pin "4") (pinfunction "4_4") (pintype "passive"))
    )
    (net (code "63") (name "/VI") (class "Default")
      (node (ref "MOS3") (pin "3") (pinfunction "S_3") (pintype "passive"))
      (node (ref "MOS4") (pin "3") (pinfunction "S_3") (pintype "passive"))
      (node (ref "Ri1") (pin "1") (pinfunction "1_1") (pintype "passive"))
    )
    (net (code "64") (name "3.3V") (class "Default")
      (node (ref "C21") (pin "1") (pinfunction "1_1") (pintype "passive"))
      (node (ref "C22") (pin "2") (pinfunction "2_2") (pintype "passive"))
      (node (ref "P3") (pin "2") (pinfunction "2_2") (pintype "passive"))
      (node (ref "R12") (pin "1") (pinfunction "1_1") (pintype "passive"))
      (node (ref "R14") (pin "1") (pinfunction "1_1") (pintype "passive"))
      (node (ref "U1") (pin "2") (pinfunction "OUT_2") (pintype "power_in"))
    )
    (net (code "65") (name "3V3") (class "Default")
      (node (ref "*1") (pin "1") (pinfunction "VBAT_1") (pintype "passive"))
      (node (ref "*1") (pin "13") (pinfunction "VDDA_13") (pintype "passive"))
      (node (ref "*1") (pin "19") (pinfunction "VDD_4_19") (pintype "passive"))
      (node (ref "*1") (pin "32") (pinfunction "VDD_1_32") (pintype "passive"))
      (node (ref "*1") (pin "48") (pinfunction "VDD_2_48") (pintype "passive"))
      (node (ref "*1") (pin "64") (pinfunction "VDD_3_64") (pintype "passive"))
      (node (ref "C11") (pin "1") (pinfunction "1_1") (pintype "passive"))
      (node (ref "C3") (pin "2") (pinfunction "2_2") (pintype "passive"))
      (node (ref "C5") (pin "1") (pinfunction "1_1") (pintype "passive"))
      (node (ref "C8") (pin "1") (pinfunction "1_1") (pintype "passive"))
      (node (ref "C9") (pin "2") (pinfunction "2_2") (pintype "passive"))
      (node (ref "P5") (pin "1") (pinfunction "1_1") (pintype "passive"))
      (node (ref "R10") (pin "1") (pinfunction "1_1") (pintype "passive"))
      (node (ref "R16") (pin "2") (pinfunction "2_2") (pintype "passive"))
      (node (ref "R3") (pin "2") (pinfunction "2_2") (pintype "passive"))
      (node (ref "R9") (pin "1") (pinfunction "1_1") (pintype "passive"))
    )
    (net (code "66") (name "5V") (class "Default")
      (node (ref "1") (pin "5") (pinfunction "VIN_5") (pintype "passive"))
      (node (ref "C10") (pin "2") (pinfunction "2_2") (pintype "passive"))
      (node (ref "C14") (pin "2") (pinfunction "2_2") (pintype "passive"))
      (node (ref "C15") (pin "1") (pinfunction "1_1") (pintype "passive"))
      (node (ref "C17") (pin "2") (pinfunction "2_2") (pintype "passive"))
      (node (ref "C20") (pin "2") (pinfunction "2_2") (pintype "passive"))
      (node (ref "C23") (pin "1") (pinfunction "1_1") (pintype "passive"))
      (node (ref "C24") (pin "2") (pinfunction "2_2") (pintype "passive"))
      (node (ref "HCPL1") (pin "1") (pinfunction "V1+_1") (pintype "passive"))
      (node (ref "HCPL1") (pin "4") (pinfunction "V2+_4") (pintype "passive"))
      (node (ref "HCPL1") (pin "8") (pinfunction "VCC_8") (pintype "passive"))
      (node (ref "L1") (pin "2") (pinfunction "2_2") (pintype "passive"))
      (node (ref "L2") (pin "1") (pinfunction "1_1") (pintype "passive"))
      (node (ref "LS1") (pin "1") (pinfunction "A_1") (pintype "passive"))
      (node (ref "LS2") (pin "1") (pinfunction "A1_1") (pintype "passive"))
      (node (ref "LS2") (pin "14") (pinfunction "VCC_14") (pintype "passive"))
      (node (ref "LS2") (pin "4") (pinfunction "A2_4") (pintype "passive"))
      (node (ref "LS2") (pin "9") (pinfunction "A3_9") (pintype "passive"))
      (node (ref "P2") (pin "3") (pinfunction "3_3") (pintype "passive"))
      (node (ref "P3") (pin "1") (pinfunction "1_1") (pintype "passive"))
      (node (ref "P4") (pin "5") (pinfunction "5_5") (pintype "passive"))
      (node (ref "R17") (pin "2") (pinfunction "2_2") (pintype "passive"))
      (node (ref "R22") (pin "2") (pinfunction "2_2") (pintype "passive"))
      (node (ref "R28") (pin "1") (pinfunction "1_1") (pintype "passive"))
      (node (ref "TJA1") (pin "3") (pinfunction "Vcc_3") (pintype "passive"))
      (node (ref "U1") (pin "3") (pinfunction "IN_3") (pintype "power_in"))
    )
    (net (code "67") (name "12V") (class "Default")
      (node (ref "C18") (pin "2") (pinfunction "2_2") (pintype "passive"))
      (node (ref "C19") (pin "2") (pinfunction "2_2") (pintype "passive"))
      (node (ref "C6") (pin "2") (pinfunction "2_2") (pintype "passive"))
      (node (ref "D1") (pin "1") (pinfunction "A_1") (pintype "passive"))
      (node (ref "D3") (pin "1") (pinfunction "A_1") (pintype "passive"))
      (node (ref "HIP1") (pin "12") (pinfunction "VDD_12") (pintype "passive"))
      (node (ref "HIP1") (pin "2") (pinfunction "BHI_2") (pintype "passive"))
      (node (ref "HIP1") (pin "7") (pinfunction "AHI_7") (pintype "passive"))
      (node (ref "P2") (pin "1") (pinfunction "1_1") (pintype "passive"))
      (node (ref "R23") (pin "2") (pinfunction "2_2") (pintype "passive"))
      (node (ref "R26") (pin "1") (pinfunction "1_1") (pintype "passive"))
      (node (ref "in1") (pin "2") (pinfunction "K_2") (pintype "passive"))
    )
    (net (code "68") (name "GND") (class "Default")
      (node (ref "*1") (pin "12") (pinfunction "VSSA_12") (pintype "passive"))
      (node (ref "*1") (pin "18") (pinfunction "VSS_4_18") (pintype "passive"))
      (node (ref "*1") (pin "31") (pinfunction "VSS_1_31") (pintype "passive"))
      (node (ref "*1") (pin "47") (pinfunction "VSS_2_47") (pintype "passive"))
      (node (ref "*1") (pin "63") (pinfunction "VSS_3_63") (pintype "passive"))
      (node (ref "C11") (pin "2") (pinfunction "2_2") (pintype "passive"))
      (node (ref "C16") (pin "1") (pinfunction "1_1") (pintype "passive"))
      (node (ref "C17") (pin "1") (pinfunction "1_1") (pintype "passive"))
      (node (ref "C2") (pin "1") (pinfunction "1_1") (pintype "passive"))
      (node (ref "C21") (pin "2") (pinfunction "2_2") (pintype "passive"))
      (node (ref "C22") (pin "1") (pinfunction "1_1") (pintype "passive"))
      (node (ref "C3") (pin "1") (pinfunction "1_1") (pintype "passive"))
      (node (ref "C4") (pin "1") (pinfunction "1_1") (pintype "passive"))
      (node (ref "C5") (pin "2") (pinfunction "2_2") (pintype "passive"))
      (node (ref "C8") (pin "2") (pinfunction "2_2") (pintype "passive"))
      (node (ref "C9") (pin "1") (pinfunction "1_1") (pintype "passive"))
      (node (ref "D2") (pin "2") (pinfunction "K_2") (pintype "passive"))
      (node (ref "HCPL1") (pin "5") (pinfunction "GND_5") (pintype "passive"))
      (node (ref "P3") (pin "3") (pinfunction "3_3") (pintype "passive"))
      (node (ref "P5") (pin "4") (pinfunction "4_4") (pintype "passive"))
      (node (ref "R15") (pin "2") (pinfunction "2_2") (pintype "passive"))
      (node (ref "R19") (pin "2") (pinfunction "2_2") (pintype "passive"))
      (node (ref "R21") (pin "2") (pinfunction "2_2") (pintype "passive"))
      (node (ref "R6") (pin "1") (pinfunction "1_1") (pintype "passive"))
      (node (ref "S1") (pin "2") (pinfunction "2_2") (pintype "passive"))
      (node (ref "TJA1") (pin "2") (pinfunction "GND_2") (pintype "passive"))
      (node (ref "TJA1") (pin "8") (pinfunction "S_8") (pintype "passive"))
      (node (ref "U1") (pin "1") (pinfunction "GND_1") (pintype "power_in"))
    )
    (net (code "69") (name "Net-(1-FB)") (class "Default")
      (node (ref "1") (pin "3") (pinfunction "FB_3") (pintype "passive"))
      (node (ref "C19") (pin "1") (pinfunction "1_1") (pintype "passive"))
      (node (ref "R23") (pin "1") (pinfunction "1_1") (pintype "passive"))
      (node (ref "R24") (pin "2") (pinfunction "2_2") (pintype "passive"))
    )
    (net (code "70") (name "Net-(1-SHDN')") (class "Default")
      (node (ref "1") (pin "4") (pinfunction "SHDN'_4") (pintype "passive"))
      (node (ref "R22") (pin "1") (pinfunction "1_1") (pintype "passive"))
    )
    (net (code "71") (name "Net-(1-SW)") (class "Default")
      (node (ref "1") (pin "1") (pinfunction "SW_1") (pintype "passive"))
      (node (ref "L2") (pin "2") (pinfunction "2_2") (pintype "passive"))
      (node (ref "in1") (pin "1") (pinfunction "A_1") (pintype "passive"))
    )
    (net (code "72") (name "Net-(D1-K)") (class "Default")
      (node (ref "C1") (pin "1") (pinfunction "1_1") (pintype "passive"))
      (node (ref "D1") (pin "2") (pinfunction "K_2") (pintype "passive"))
      (node (ref "HIP1") (pin "1") (pinfunction "BHB_1") (pintype "passive"))
    )
    (net (code "73") (name "Net-(D2-A)") (class "Default")
      (node (ref "D2") (pin "1") (pinfunction "A_1") (pintype "passive"))
      (node (ref "R9") (pin "2") (pinfunction "2_2") (pintype "passive"))
    )
    (net (code "74") (name "Net-(D3-K)") (class "Default")
      (node (ref "C7") (pin "1") (pinfunction "1_1") (pintype "passive"))
      (node (ref "D3") (pin "2") (pinfunction "K_2") (pintype "passive"))
      (node (ref "HIP1") (pin "9") (pinfunction "AHB_9") (pintype "passive"))
    )
    (net (code "75") (name "Net-(D4-A)") (class "Default")
      (node (ref "D4") (pin "1") (pinfunction "A_1") (pintype "passive"))
      (node (ref "R10") (pin "2") (pinfunction "2_2") (pintype "passive"))
    )
    (net (code "76") (name "Net-(D5-K)") (class "Default")
      (node (ref "C12") (pin "2") (pinfunction "2_2") (pintype "passive"))
      (node (ref "D5") (pin "2") (pinfunction "K_2") (pintype "passive"))
      (node (ref "L1") (pin "1") (pinfunction "1_1") (pintype "passive"))
      (node (ref "TPS1") (pin "8") (pinfunction "PH_8") (pintype "passive"))
    )
    (net (code "77") (name "Net-(D6-A)") (class "Default")
      (node (ref "D6") (pin "1") (pinfunction "A_1") (pintype "passive"))
      (node (ref "R26") (pin "2") (pinfunction "2_2") (pintype "passive"))
    )
    (net (code "78") (name "Net-(D7-A)") (class "Default")
      (node (ref "D7") (pin "1") (pinfunction "A_1") (pintype "passive"))
      (node (ref "R27") (pin "2") (pinfunction "2_2") (pintype "passive"))
    )
    (net (code "79") (name "Net-(D8-A)") (class "Default")
      (node (ref "D8") (pin "1") (pinfunction "A_1") (pintype "passive"))
      (node (ref "R28") (pin "2") (pinfunction "2_2") (pintype "passive"))
    )
    (net (code "80") (name "Net-(HCPL1-V1-)") (class "Default")
      (node (ref "HCPL1") (pin "2") (pinfunction "V1-_2") (pintype "passive"))
      (node (ref "R11") (pin "1") (pinfunction "1_1") (pintype "passive"))
    )
    (net (code "81") (name "Net-(HCPL1-V2-)") (class "Default")
      (node (ref "HCPL1") (pin "3") (pinfunction "V2-_3") (pintype "passive"))
      (node (ref "R13") (pin "1") (pinfunction "1_1") (pintype "passive"))
    )
    (net (code "82") (name "Net-(HIP1-AHO)") (class "Default")
      (node (ref "HIP1") (pin "10") (pinfunction "AHO_10") (pintype "passive"))
      (node (ref "R2") (pin "2") (pinfunction "2_2") (pintype "passive"))
    )
    (net (code "83") (name "Net-(HIP1-ALO)") (class "Default")
      (node (ref "HIP1") (pin "13") (pinfunction "ALO_13") (pintype "passive"))
      (node (ref "R7") (pin "2") (pinfunction "2_2") (pintype "passive"))
    )
    (net (code "84") (name "Net-(HIP1-BHO)") (class "Default")
      (node (ref "HIP1") (pin "16") (pinfunction "BHO_16") (pintype "passive"))
      (node (ref "R1") (pin "1") (pinfunction "1_1") (pintype "passive"))
    )
    (net (code "85") (name "Net-(HIP1-BLO)") (class "Default")
      (node (ref "HIP1") (pin "14") (pinfunction "BLO_14") (pintype "passive"))
      (node (ref "R4") (pin "1") (pinfunction "1_1") (pintype "passive"))
    )
    (net (code "86") (name "Net-(HIP1-DEL)") (class "Default")
      (node (ref "HIP1") (pin "5") (pinfunction "DEL_5") (pintype "passive"))
      (node (ref "R8") (pin "2") (pinfunction "2_2") (pintype "passive"))
    )
    (net (code "87") (name "Net-(LS1-B)") (class "Default")
      (node (ref "LS1") (pin "2") (pinfunction "B_2") (pintype "passive"))
      (node (ref "Q1") (pin "3") (pinfunction "C_3") (pintype "passive"))
    )
    (net (code "88") (name "Net-(MOS1-G)") (class "Default")
      (node (ref "MOS1") (pin "1") (pinfunction "G_1") (pintype "passive"))
      (node (ref "R2") (pin "1") (pinfunction "1_1") (pintype "passive"))
    )
    (net (code "89") (name "Net-(MOS2-G)") (class "Default")
      (node (ref "MOS2") (pin "1") (pinfunction "G_1") (pintype "passive"))
      (node (ref "R1") (pin "2") (pinfunction "2_2") (pintype "passive"))
    )
    (net (code "90") (name "Net-(MOS3-G)") (class "Default")
      (node (ref "MOS3") (pin "1") (pinfunction "G_1") (pintype "passive"))
      (node (ref "R7") (pin "1") (pinfunction "1_1") (pintype "passive"))
    )
    (net (code "91") (name "Net-(MOS4-G)") (class "Default")
      (node (ref "MOS4") (pin "1") (pinfunction "G_1") (pintype "passive"))
      (node (ref "R4") (pin "2") (pinfunction "2_2") (pintype "passive"))
    )
    (net (code "92") (name "Net-(P6-Pad1)") (class "Default")
      (node (ref "P6") (pin "1") (pinfunction "1_1") (pintype "passive"))
      (node (ref "R25") (pin "2") (pinfunction "2_2") (pintype "passive"))
    )
    (net (code "93") (name "Net-(Q1-B)") (class "Default")
      (node (ref "Q1") (pin "1") (pinfunction "B_1") (pintype "passive"))
      (node (ref "R20") (pin "2") (pinfunction "2_2") (pintype "passive"))
    )
    (net (code "94") (name "Net-(TPS1-BOOT)") (class "Default")
      (node (ref "C12") (pin "1") (pinfunction "1_1") (pintype "passive"))
      (node (ref "TPS1") (pin "1") (pinfunction "BOOT_1") (pintype "passive"))
    )
    (net (code "95") (name "Net-(TPS1-VSNS)") (class "Default")
      (node (ref "R17") (pin "1") (pinfunction "1_1") (pintype "passive"))
      (node (ref "R18") (pin "2") (pinfunction "2_2") (pintype "passive"))
      (node (ref "TPS1") (pin "4") (pinfunction "VSNS_4") (pintype "passive"))
    )
    (net (code "96") (name "PGND") (class "Default")
      (node (ref "1") (pin "2") (pinfunction "GND_2") (pintype "passive"))
      (node (ref "C10") (pin "1") (pinfunction "1_1") (pintype "passive"))
      (node (ref "C13") (pin "1") (pinfunction "1_1") (pintype "passive"))
      (node (ref "C14") (pin "1") (pinfunction "1_1") (pintype "passive"))
      (node (ref "C15") (pin "2") (pinfunction "2_2") (pintype "passive"))
      (node (ref "C18") (pin "1") (pinfunction "1_1") (pintype "passive"))
      (node (ref "C20") (pin "1") (pinfunction "1_1") (pintype "passive"))
      (node (ref "C23") (pin "2") (pinfunction "2_2") (pintype "passive"))
      (node (ref "C24") (pin "1") (pinfunction "1_1") (pintype "passive"))
      (node (ref "C6") (pin "1") (pinfunction "1_1") (pintype "passive"))
      (node (ref "CV1") (pin "2") (pinfunction "2_2") (pintype "passive"))
      (node (ref "CV2") (pin "2") (pinfunction "2_2") (pintype "passive"))
      (node (ref "D5") (pin "1") (pinfunction "A_1") (pintype "passive"))
      (node (ref "D6") (pin "2") (pinfunction "K_2") (pintype "passive"))
      (node (ref "D7") (pin "2") (pinfunction "K_2") (pintype "passive"))
      (node (ref "D8") (pin "2") (pinfunction "K_2") (pintype "passive"))
      (node (ref "HIP1") (pin "6") (pinfunction "VSS_6") (pintype "passive"))
      (node (ref "LS2") (pin "11") (pinfunction "Y4_11") (pintype "passive"))
      (node (ref "LS2") (pin "12") (pinfunction "A4_12") (pintype "passive"))
      (node (ref "LS2") (pin "13") (pinfunction "B4_13") (pintype "passive"))
      (node (ref "LS2") (pin "7") (pinfunction "GND_7") (pintype "passive"))
      (node (ref "P2") (pin "6") (pinfunction "6_6") (pintype "passive"))
      (node (ref "P4") (pin "2") (pinfunction "2_2") (pintype "passive"))
      (node (ref "P4") (pin "8") (pinfunction "8_8") (pintype "passive"))
      (node (ref "Q1") (pin "2") (pinfunction "E_2") (pintype "passive"))
      (node (ref "R15") (pin "1") (pinfunction "1_1") (pintype "passive"))
      (node (ref "R18") (pin "1") (pinfunction "1_1") (pintype "passive"))
      (node (ref "R24") (pin "1") (pinfunction "1_1") (pintype "passive"))
      (node (ref "R8") (pin "1") (pinfunction "1_1") (pintype "passive"))
      (node (ref "Ri1") (pin "2") (pinfunction "2_2") (pintype "passive"))
      (node (ref "TPS1") (pin "6") (pinfunction "GND_6") (pintype "passive"))
      (node (ref "TPS1") (pin "9") (pinfunction "PWPD_9") (pintype "passive"))
    )
    (net (code "97") (name "VIN") (class "Default")
      (node (ref "C13") (pin "2") (pinfunction "2_2") (pintype "passive"))
      (node (ref "CV1") (pin "1") (pinfunction "1_1") (pintype "passive"))
      (node (ref "CV2") (pin "1") (pinfunction "1_1") (pintype "passive"))
      (node (ref "MOS1") (pin "4") (pinfunction "D_4") (pintype "passive"))
      (node (ref "MOS2") (pin "4") (pinfunction "D_4") (pintype "passive"))
      (node (ref "P4") (pin "1") (pinfunction "1_1") (pintype "passive"))
      (node (ref "R27") (pin "1") (pinfunction "1_1") (pintype "passive"))
      (node (ref "TPS1") (pin "7") (pinfunction "VIN_7") (pintype "passive"))
    )
    (net (code "98") (name "unconnected-(P2-Pad2)") (class "Default")
      (node (ref "P2") (pin "2") (pinfunction "2_2") (pintype "passive"))
    )
    (net (code "99") (name "unconnected-(P2-Pad4)") (class "Default")
      (node (ref "P2") (pin "4") (pinfunction "4_4") (pintype "passive"))
    )
    (net (code "100") (name "unconnected-(P2-Pad5)") (class "Default")
      (node (ref "P2") (pin "5") (pinfunction "5_5") (pintype "passive"))
    )
    (net (code "101") (name "unconnected-(TJA1-Vref-Pad5)") (class "Default")
      (node (ref "TJA1") (pin "5") (pinfunction "Vref_5") (pintype "passive"))
    )
    (net (code "102") (name "unconnected-(TPS1-ENA-Pad5)") (class "Default")
      (node (ref "TPS1") (pin "5") (pinfunction "ENA_5") (pintype "passive"))
    )
    (net (code "103") (name "unconnected-(TPS1-NC-Pad2)") (class "Default")
      (node (ref "TPS1") (pin "2") (pinfunction "NC_2") (pintype "passive"))
    )
    (net (code "104") (name "unconnected-(TPS1-NC-Pad3)") (class "Default")
      (node (ref "TPS1") (pin "3") (pinfunction "NC_3") (pintype "passive"))
    )
    (net (code "105") (name "unconnected-(U1-TAB-Pad4)") (class "Default")
      (node (ref "U1") (pin "4") (pinfunction "TAB_4") (pintype "power_in"))
    )
  )
)
